# FETs.net
KiCad netlist of a schematic drawn in Altium Designer
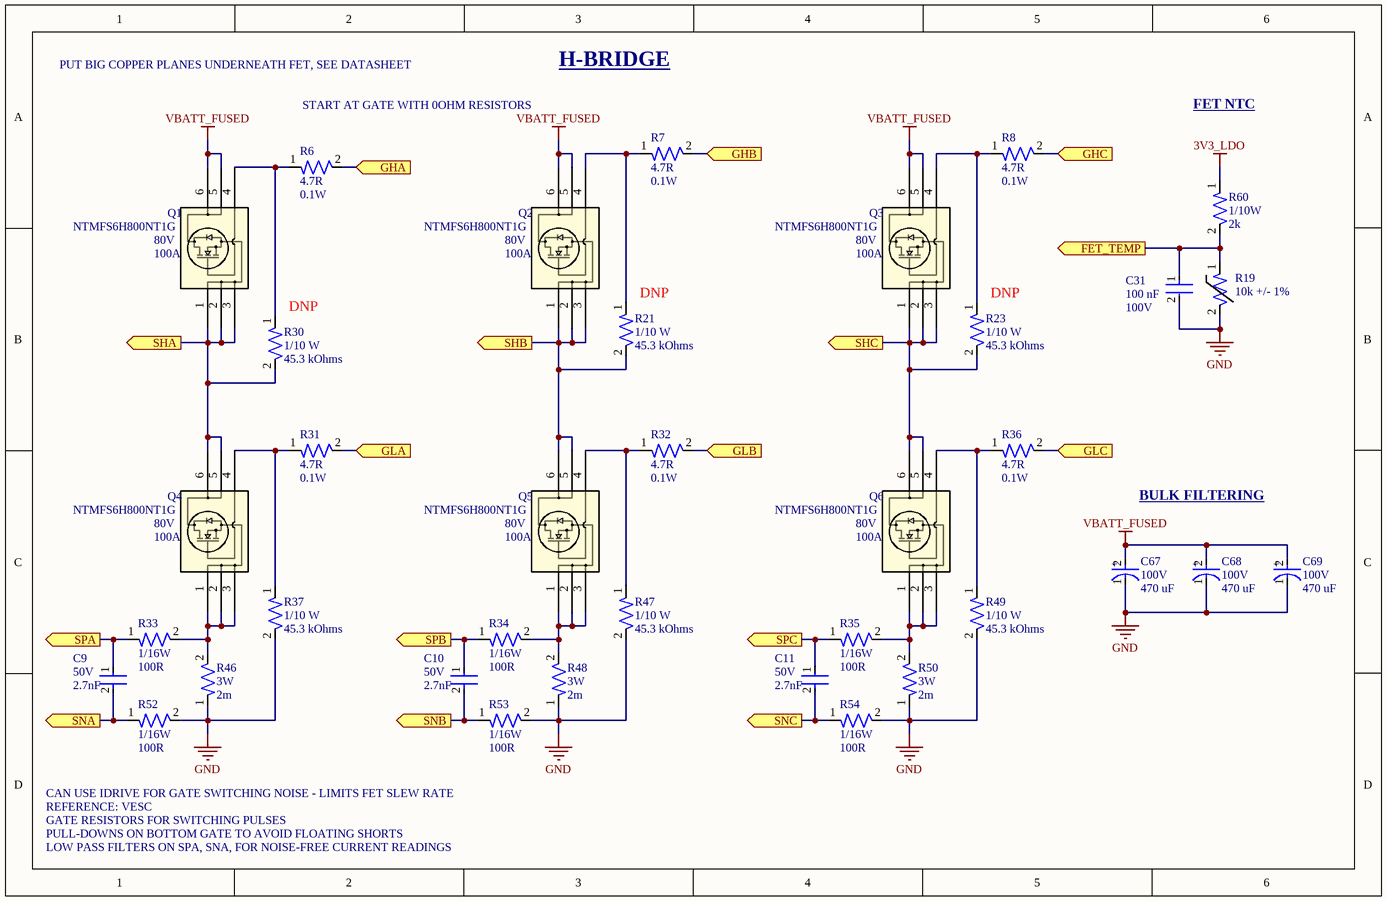
[diagram p0: FETs.SchDoc]

(export (version "E")
  (design (tool "Eeschema 10.0.6"))
  (components
    (comp (ref "C9")
      (value "GRM2165C1H272JA01D")
      (footprint "CAP-0805")
      (description "CAP CER 2700PF 50V C0G/NP0 0805")
      (fields (field (name "VOLTAGE") "50V") (field (name "CAPACITANCE") "2.7nF"))
      (libsource (lib "JLC_25") (part "CAP-2.7N-0001"))
    )
    (comp (ref "C10")
      (value "GRM2165C1H272JA01D")
      (footprint "CAP-0805")
      (description "CAP CER 2700PF 50V C0G/NP0 0805")
      (fields (field (name "VOLTAGE") "50V") (field (name "CAPACITANCE") "2.7nF"))
      (libsource (lib "JLC_25") (part "CAP-2.7N-0001"))
    )
    (comp (ref "C11")
      (value "GRM2165C1H272JA01D")
      (footprint "CAP-0805")
      (description "CAP CER 2700PF 50V C0G/NP0 0805")
      (fields (field (name "VOLTAGE") "50V") (field (name "CAPACITANCE") "2.7nF"))
      (libsource (lib "JLC_25") (part "CAP-2.7N-0001"))
    )
    (comp (ref "C31")
      (value "GRM188R72A104KA35D")
      (footprint "CAP-0603")
      (description "CAP CER 100NF 100V X7R 0603")
      (fields (field (name "CAPACITANCE") "100 nF") (field (name "VOLTAGE") "100V"))
      (libsource (lib "JLC_25") (part "CAP-1U-0002"))
    )
    (comp (ref "C67")
      (value "ESH477M100AM2AA")
      (footprint "CAP-470U-0001")
      (description "CAP ALUM 470UF 20% 100V RADIAL")
      (fields (field (name "VOLTAGE") "100V") (field (name "CAPACITANCE") "470 uF"))
      (libsource (lib "JLC_25") (part "CAP-470U-0001"))
    )
    (comp (ref "C68")
      (value "ESH477M100AM2AA")
      (footprint "CAP-470U-0001")
      (description "CAP ALUM 470UF 20% 100V RADIAL")
      (fields (field (name "VOLTAGE") "100V") (field (name "CAPACITANCE") "470 uF"))
      (libsource (lib "JLC_25") (part "CAP-470U-0001"))
    )
    (comp (ref "C69")
      (value "ESH477M100AM2AA")
      (footprint "CAP-470U-0001")
      (description "CAP ALUM 470UF 20% 100V RADIAL")
      (fields (field (name "VOLTAGE") "100V") (field (name "CAPACITANCE") "470 uF"))
      (libsource (lib "JLC_25") (part "CAP-470U-0001"))
    )
    (comp (ref "Q1")
      (value "NTMFS6H800NT1G")
      (footprint "DFN6_5X6_SO8FL_488AA_ONS")
      (description "N-Channel 80 V 28A (Ta), 203A (Tc) 3.8W (Ta), 200W (Tc) Surface Mount 5-DFN (5x6) (8-SOFL)")
      (fields
        (field (name "MANUFACTURER_PART_NUMBER") "TPH2R506PL")
        (field (name "VDSS") "80V")
        (field (name "DRAIN CURRENT") "100A")
      )
      (libsource (lib "MasterLib") (part "NTMFS6H800NT1G"))
    )
    (comp (ref "Q2")
      (value "NTMFS6H800NT1G")
      (footprint "DFN6_5X6_SO8FL_488AA_ONS")
      (description "N-Channel 80 V 28A (Ta), 203A (Tc) 3.8W (Ta), 200W (Tc) Surface Mount 5-DFN (5x6) (8-SOFL)")
      (fields
        (field (name "MANUFACTURER_PART_NUMBER") "TPH2R506PL")
        (field (name "VDSS") "80V")
        (field (name "DRAIN CURRENT") "100A")
      )
      (libsource (lib "MasterLib") (part "NTMFS6H800NT1G"))
    )
    (comp (ref "Q3")
      (value "NTMFS6H800NT1G")
      (footprint "DFN6_5X6_SO8FL_488AA_ONS")
      (description "N-Channel 80 V 28A (Ta), 203A (Tc) 3.8W (Ta), 200W (Tc) Surface Mount 5-DFN (5x6) (8-SOFL)")
      (fields
        (field (name "MANUFACTURER_PART_NUMBER") "TPH2R506PL")
        (field (name "VDSS") "80V")
        (field (name "DRAIN CURRENT") "100A")
      )
      (libsource (lib "MasterLib") (part "NTMFS6H800NT1G"))
    )
    (comp (ref "Q4")
      (value "NTMFS6H800NT1G")
      (footprint "DFN6_5X6_SO8FL_488AA_ONS")
      (description "N-Channel 80 V 28A (Ta), 203A (Tc) 3.8W (Ta), 200W (Tc) Surface Mount 5-DFN (5x6) (8-SOFL)")
      (fields
        (field (name "MANUFACTURER_PART_NUMBER") "TPH2R506PL")
        (field (name "VDSS") "80V")
        (field (name "DRAIN CURRENT") "100A")
      )
      (libsource (lib "MasterLib") (part "NTMFS6H800NT1G"))
    )
    (comp (ref "Q5")
      (value "NTMFS6H800NT1G")
      (footprint "DFN6_5X6_SO8FL_488AA_ONS")
      (description "N-Channel 80 V 28A (Ta), 203A (Tc) 3.8W (Ta), 200W (Tc) Surface Mount 5-DFN (5x6) (8-SOFL)")
      (fields
        (field (name "MANUFACTURER_PART_NUMBER") "TPH2R506PL")
        (field (name "VDSS") "80V")
        (field (name "DRAIN CURRENT") "100A")
      )
      (libsource (lib "MasterLib") (part "NTMFS6H800NT1G"))
    )
    (comp (ref "Q6")
      (value "NTMFS6H800NT1G")
      (footprint "DFN6_5X6_SO8FL_488AA_ONS")
      (description "N-Channel 80 V 28A (Ta), 203A (Tc) 3.8W (Ta), 200W (Tc) Surface Mount 5-DFN (5x6) (8-SOFL)")
      (fields
        (field (name "MANUFACTURER_PART_NUMBER") "TPH2R506PL")
        (field (name "VDSS") "80V")
        (field (name "DRAIN CURRENT") "100A")
      )
      (libsource (lib "MasterLib") (part "NTMFS6H800NT1G"))
    )
    (comp (ref "R6")
      (value "RMCF0603FT4R70")
      (footprint "RES-0603")
      (description "4.7 Ohms ±1% 0.1W, 1/10W Chip Resistor 0603 (1608 Metric) Automotive AEC-Q200 Thick Film")
      (fields
        (field (name "TOLERANCE") "1%")
        (field (name "RESISTANCE") "4.7R")
        (field (name "POWER") "0.1W")
      )
      (libsource (lib "JLC_25") (part "RES-4.7-0001"))
    )
    (comp (ref "R7")
      (value "RMCF0603FT4R70")
      (footprint "RES-0603")
      (description "4.7 Ohms ±1% 0.1W, 1/10W Chip Resistor 0603 (1608 Metric) Automotive AEC-Q200 Thick Film")
      (fields
        (field (name "TOLERANCE") "1%")
        (field (name "RESISTANCE") "4.7R")
        (field (name "POWER") "0.1W")
      )
      (libsource (lib "JLC_25") (part "RES-4.7-0001"))
    )
    (comp (ref "R8")
      (value "RMCF0603FT4R70")
      (footprint "RES-0603")
      (description "4.7 Ohms ±1% 0.1W, 1/10W Chip Resistor 0603 (1608 Metric) Automotive AEC-Q200 Thick Film")
      (fields
        (field (name "TOLERANCE") "1%")
        (field (name "RESISTANCE") "4.7R")
        (field (name "POWER") "0.1W")
      )
      (libsource (lib "JLC_25") (part "RES-4.7-0001"))
    )
    (comp (ref "R19")
      (value "NCU18XH103F60RB")
      (footprint "RES-0603")
      (description "NTC Thermistor 10k 0603 (1608 Metric)")
      (fields
        (field (name "MANUFACTURER PART NUMBER") "TMP6431DECR")
        (field (name "MANUFACTURER") "Texas Instruments")
        (field (name "RESISTANCE") "10k +/- 1%")
      )
      (libsource (lib "MasterLib") (part "THERM-10K-0001"))
    )
    (comp (ref "R21")
      (value "RC0603FR-0745K3L")
      (footprint "RES-0603")
      (description "45.3 kOhms ±1% 0.1W, 1/10W Chip Resistor 0603 (1608 Metric) Moisture Resistant Thick Film")
      (fields
        (field (name "TOLERANCE") "+/- 1%")
        (field (name "POWER") "1/10 W")
        (field (name "RESISTANCE") "45.3 kOhms")
      )
      (libsource (lib "MasterLib") (part "RES-45.3K-0001"))
    )
    (comp (ref "R23")
      (value "RC0603FR-0745K3L")
      (footprint "RES-0603")
      (description "45.3 kOhms ±1% 0.1W, 1/10W Chip Resistor 0603 (1608 Metric) Moisture Resistant Thick Film")
      (fields
        (field (name "TOLERANCE") "+/- 1%")
        (field (name "POWER") "1/10 W")
        (field (name "RESISTANCE") "45.3 kOhms")
      )
      (libsource (lib "MasterLib") (part "RES-45.3K-0001"))
    )
    (comp (ref "R30")
      (value "RC0603FR-0745K3L")
      (footprint "RES-0603")
      (description "45.3 kOhms ±1% 0.1W, 1/10W Chip Resistor 0603 (1608 Metric) Moisture Resistant Thick Film")
      (fields
        (field (name "TOLERANCE") "+/- 1%")
        (field (name "POWER") "1/10 W")
        (field (name "RESISTANCE") "45.3 kOhms")
      )
      (libsource (lib "MasterLib") (part "RES-45.3K-0001"))
    )
    (comp (ref "R31")
      (value "RMCF0603FT4R70")
      (footprint "RES-0603")
      (description "4.7 Ohms ±1% 0.1W, 1/10W Chip Resistor 0603 (1608 Metric) Automotive AEC-Q200 Thick Film")
      (fields
        (field (name "TOLERANCE") "1%")
        (field (name "RESISTANCE") "4.7R")
        (field (name "POWER") "0.1W")
      )
      (libsource (lib "JLC_25") (part "RES-4.7-0001"))
    )
    (comp (ref "R32")
      (value "RMCF0603FT4R70")
      (footprint "RES-0603")
      (description "4.7 Ohms ±1% 0.1W, 1/10W Chip Resistor 0603 (1608 Metric) Automotive AEC-Q200 Thick Film")
      (fields
        (field (name "TOLERANCE") "1%")
        (field (name "RESISTANCE") "4.7R")
        (field (name "POWER") "0.1W")
      )
      (libsource (lib "JLC_25") (part "RES-4.7-0001"))
    )
    (comp (ref "R33")
      (value "RC0402FR-07100RL")
      (footprint "RES-0402")
      (description "RES 100 OHM 1% 1/16W 0402")
      (fields
        (field (name "TOLERANCE") "1%")
        (field (name "POWER") "1/16W")
        (field (name "RESISTANCE") "100R")
      )
      (libsource (lib "JLC_25") (part "RES-100-0001"))
    )
    (comp (ref "R34")
      (value "RC0402FR-07100RL")
      (footprint "RES-0402")
      (description "RES 100 OHM 1% 1/16W 0402")
      (fields
        (field (name "TOLERANCE") "1%")
        (field (name "POWER") "1/16W")
        (field (name "RESISTANCE") "100R")
      )
      (libsource (lib "JLC_25") (part "RES-100-0001"))
    )
    (comp (ref "R35")
      (value "RC0402FR-07100RL")
      (footprint "RES-0402")
      (description "RES 100 OHM 1% 1/16W 0402")
      (fields
        (field (name "TOLERANCE") "1%")
        (field (name "POWER") "1/16W")
        (field (name "RESISTANCE") "100R")
      )
      (libsource (lib "JLC_25") (part "RES-100-0001"))
    )
    (comp (ref "R36")
      (value "RMCF0603FT4R70")
      (footprint "RES-0603")
      (description "4.7 Ohms ±1% 0.1W, 1/10W Chip Resistor 0603 (1608 Metric) Automotive AEC-Q200 Thick Film")
      (fields
        (field (name "TOLERANCE") "1%")
        (field (name "RESISTANCE") "4.7R")
        (field (name "POWER") "0.1W")
      )
      (libsource (lib "JLC_25") (part "RES-4.7-0001"))
    )
    (comp (ref "R37")
      (value "RC0603FR-0745K3L")
      (footprint "RES-0603")
      (description "45.3 kOhms ±1% 0.1W, 1/10W Chip Resistor 0603 (1608 Metric) Moisture Resistant Thick Film")
      (fields
        (field (name "TOLERANCE") "+/- 1%")
        (field (name "POWER") "1/10 W")
        (field (name "RESISTANCE") "45.3 kOhms")
      )
      (libsource (lib "MasterLib") (part "RES-45.3K-0001"))
    )
    (comp (ref "R46")
      (value "CSNL2512FT2L00")
      (footprint "STA_CSNL25122_STP")
      (description "2 mOhms ±1% 3W Chip Resistor 2512 (6332 Metric) Current Sense, Moisture Resistant Metal Element")
      (fields (field (name "TOLERANCE") "1%") (field (name "POWER") "3W") (field (name "RESISTANCE") "2m"))
      (libsource (lib "JLC_25") (part "RES-2m-0001"))
    )
    (comp (ref "R47")
      (value "RC0603FR-0745K3L")
      (footprint "RES-0603")
      (description "45.3 kOhms ±1% 0.1W, 1/10W Chip Resistor 0603 (1608 Metric) Moisture Resistant Thick Film")
      (fields
        (field (name "TOLERANCE") "+/- 1%")
        (field (name "POWER") "1/10 W")
        (field (name "RESISTANCE") "45.3 kOhms")
      )
      (libsource (lib "MasterLib") (part "RES-45.3K-0001"))
    )
    (comp (ref "R48")
      (value "CSNL2512FT2L00")
      (footprint "STA_CSNL25122_STP")
      (description "2 mOhms ±1% 3W Chip Resistor 2512 (6332 Metric) Current Sense, Moisture Resistant Metal Element")
      (fields (field (name "TOLERANCE") "1%") (field (name "POWER") "3W") (field (name "RESISTANCE") "2m"))
      (libsource (lib "JLC_25") (part "RES-2m-0001"))
    )
    (comp (ref "R49")
      (value "RC0603FR-0745K3L")
      (footprint "RES-0603")
      (description "45.3 kOhms ±1% 0.1W, 1/10W Chip Resistor 0603 (1608 Metric) Moisture Resistant Thick Film")
      (fields
        (field (name "TOLERANCE") "+/- 1%")
        (field (name "POWER") "1/10 W")
        (field (name "RESISTANCE") "45.3 kOhms")
      )
      (libsource (lib "MasterLib") (part "RES-45.3K-0001"))
    )
    (comp (ref "R50")
      (value "CSNL2512FT2L00")
      (footprint "STA_CSNL25122_STP")
      (description "2 mOhms ±1% 3W Chip Resistor 2512 (6332 Metric) Current Sense, Moisture Resistant Metal Element")
      (fields (field (name "TOLERANCE") "1%") (field (name "POWER") "3W") (field (name "RESISTANCE") "2m"))
      (libsource (lib "JLC_25") (part "RES-2m-0001"))
    )
    (comp (ref "R52")
      (value "RC0402FR-07100RL")
      (footprint "RES-0402")
      (description "RES 100 OHM 1% 1/16W 0402")
      (fields
        (field (name "TOLERANCE") "1%")
        (field (name "POWER") "1/16W")
        (field (name "RESISTANCE") "100R")
      )
      (libsource (lib "JLC_25") (part "RES-100-0001"))
    )
    (comp (ref "R53")
      (value "RC0402FR-07100RL")
      (footprint "RES-0402")
      (description "RES 100 OHM 1% 1/16W 0402")
      (fields
        (field (name "TOLERANCE") "1%")
        (field (name "POWER") "1/16W")
        (field (name "RESISTANCE") "100R")
      )
      (libsource (lib "JLC_25") (part "RES-100-0001"))
    )
    (comp (ref "R54")
      (value "RC0402FR-07100RL")
      (footprint "RES-0402")
      (description "RES 100 OHM 1% 1/16W 0402")
      (fields
        (field (name "TOLERANCE") "1%")
        (field (name "POWER") "1/16W")
        (field (name "RESISTANCE") "100R")
      )
      (libsource (lib "JLC_25") (part "RES-100-0001"))
    )
    (comp (ref "R60")
      (value "RC0603JR-072KL")
      (footprint "RES-0603")
      (description "RES 2K OHM 5% 1/10W 0603")
      (fields (field (name "POWER") "1/10W") (field (name "RESISTANCE") "2k"))
      (libsource (lib "JLC_25") (part "RES-13.7K-0001"))
    )
  )
  (nets
    (net (code "1") (name "/FET_TEMP") (class "Default")
      (node (ref "C31") (pin "1") (pinfunction "1_1") (pintype "passive"))
      (node (ref "R19") (pin "1") (pinfunction "1_1") (pintype "passive"))
      (node (ref "R60") (pin "2") (pinfunction "2_2") (pintype "passive"))
    )
    (net (code "2") (name "/GHA") (class "Default")
      (node (ref "R6") (pin "2") (pinfunction "2_2") (pintype "passive"))
    )
    (net (code "3") (name "/GHB") (class "Default")
      (node (ref "R7") (pin "2") (pinfunction "2_2") (pintype "passive"))
    )
    (net (code "4") (name "/GHC") (class "Default")
      (node (ref "R8") (pin "2") (pinfunction "2_2") (pintype "passive"))
    )
    (net (code "5") (name "/GLA") (class "Default")
      (node (ref "R31") (pin "2") (pinfunction "2_2") (pintype "passive"))
    )
    (net (code "6") (name "/GLB") (class "Default")
      (node (ref "R32") (pin "2") (pinfunction "2_2") (pintype "passive"))
    )
    (net (code "7") (name "/GLC") (class "Default")
      (node (ref "R36") (pin "2") (pinfunction "2_2") (pintype "passive"))
    )
    (net (code "8") (name "/SHA") (class "Default")
      (node (ref "Q1") (pin "1") (pinfunction "1_1") (pintype "passive"))
      (node (ref "Q1") (pin "2") (pinfunction "2_2") (pintype "passive"))
      (node (ref "Q1") (pin "3") (pinfunction "3_3") (pintype "passive"))
      (node (ref "Q4") (pin "5") (pinfunction "5_5") (pintype "passive"))
      (node (ref "Q4") (pin "6") (pinfunction "6_6") (pintype "passive"))
      (node (ref "R30") (pin "2") (pinfunction "2_2") (pintype "passive"))
    )
    (net (code "9") (name "/SHB") (class "Default")
      (node (ref "Q2") (pin "1") (pinfunction "1_1") (pintype "passive"))
      (node (ref "Q2") (pin "2") (pinfunction "2_2") (pintype "passive"))
      (node (ref "Q2") (pin "3") (pinfunction "3_3") (pintype "passive"))
      (node (ref "Q5") (pin "5") (pinfunction "5_5") (pintype "passive"))
      (node (ref "Q5") (pin "6") (pinfunction "6_6") (pintype "passive"))
      (node (ref "R21") (pin "2") (pinfunction "2_2") (pintype "passive"))
    )
    (net (code "10") (name "/SHC") (class "Default")
      (node (ref "Q3") (pin "1") (pinfunction "1_1") (pintype "passive"))
      (node (ref "Q3") (pin "2") (pinfunction "2_2") (pintype "passive"))
      (node (ref "Q3") (pin "3") (pinfunction "3_3") (pintype "passive"))
      (node (ref "Q6") (pin "5") (pinfunction "5_5") (pintype "passive"))
      (node (ref "Q6") (pin "6") (pinfunction "6_6") (pintype "passive"))
      (node (ref "R23") (pin "2") (pinfunction "2_2") (pintype "passive"))
    )
    (net (code "11") (name "/SNA") (class "Default")
      (node (ref "C9") (pin "2") (pinfunction "2_2") (pintype "passive"))
      (node (ref "R52") (pin "1") (pinfunction "1_1") (pintype "passive"))
    )
    (net (code "12") (name "/SNB") (class "Default")
      (node (ref "C10") (pin "2") (pinfunction "2_2") (pintype "passive"))
      (node (ref "R53") (pin "1") (pinfunction "1_1") (pintype "passive"))
    )
    (net (code "13") (name "/SNC") (class "Default")
      (node (ref "C11") (pin "2") (pinfunction "2_2") (pintype "passive"))
      (node (ref "R54") (pin "1") (pinfunction "1_1") (pintype "passive"))
    )
    (net (code "14") (name "/SPA") (class "Default")
      (node (ref "C9") (pin "1") (pinfunction "1_1") (pintype "passive"))
      (node (ref "R33") (pin "1") (pinfunction "1_1") (pintype "passive"))
    )
    (net (code "15") (name "/SPB") (class "Default")
      (node (ref "C10") (pin "1") (pinfunction "1_1") (pintype "passive"))
      (node (ref "R34") (pin "1") (pinfunction "1_1") (pintype "passive"))
    )
    (net (code "16") (name "/SPC") (class "Default")
      (node (ref "C11") (pin "1") (pinfunction "1_1") (pintype "passive"))
      (node (ref "R35") (pin "1") (pinfunction "1_1") (pintype "passive"))
    )
    (net (code "17") (name "3V3_LDO") (class "Default")
      (node (ref "R60") (pin "1") (pinfunction "1_1") (pintype "passive"))
    )
    (net (code "18") (name "GND") (class "Default")
      (node (ref "C31") (pin "2") (pinfunction "2_2") (pintype "passive"))
      (node (ref "C67") (pin "1") (pinfunction "2_1") (pintype "passive"))
      (node (ref "C68") (pin "1") (pinfunction "2_1") (pintype "passive"))
      (node (ref "C69") (pin "1") (pinfunction "2_1") (pintype "passive"))
      (node (ref "R19") (pin "2") (pinfunction "2_2") (pintype "passive"))
      (node (ref "R37") (pin "2") (pinfunction "2_2") (pintype "passive"))
      (node (ref "R46") (pin "1") (pinfunction "1_1") (pintype "passive"))
      (node (ref "R47") (pin "2") (pinfunction "2_2") (pintype "passive"))
      (node (ref "R48") (pin "1") (pinfunction "1_1") (pintype "passive"))
      (node (ref "R49") (pin "2") (pinfunction "2_2") (pintype "passive"))
      (node (ref "R50") (pin "1") (pinfunction "1_1") (pintype "passive"))
      (node (ref "R52") (pin "2") (pinfunction "2_2") (pintype "passive"))
      (node (ref "R53") (pin "2") (pinfunction "2_2") (pintype "passive"))
      (node (ref "R54") (pin "2") (pinfunction "2_2") (pintype "passive"))
    )
    (net (code "19") (name "Net-(Q1-Pad4)") (class "Default")
      (node (ref "Q1") (pin "4") (pinfunction "4_4") (pintype "passive"))
      (node (ref "R30") (pin "1") (pinfunction "1_1") (pintype "passive"))
      (node (ref "R6") (pin "1") (pinfunction "1_1") (pintype "passive"))
    )
    (net (code "20") (name "Net-(Q2-Pad4)") (class "Default")
      (node (ref "Q2") (pin "4") (pinfunction "4_4") (pintype "passive"))
      (node (ref "R21") (pin "1") (pinfunction "1_1") (pintype "passive"))
      (node (ref "R7") (pin "1") (pinfunction "1_1") (pintype "passive"))
    )
    (net (code "21") (name "Net-(Q3-Pad4)") (class "Default")
      (node (ref "Q3") (pin "4") (pinfunction "4_4") (pintype "passive"))
      (node (ref "R23") (pin "1") (pinfunction "1_1") (pintype "passive"))
      (node (ref "R8") (pin "1") (pinfunction "1_1") (pintype "passive"))
    )
    (net (code "22") (name "Net-(Q4-Pad1)") (class "Default")
      (node (ref "Q4") (pin "1") (pinfunction "1_1") (pintype "passive"))
      (node (ref "Q4") (pin "2") (pinfunction "2_2") (pintype "passive"))
      (node (ref "Q4") (pin "3") (pinfunction "3_3") (pintype "passive"))
      (node (ref "R33") (pin "2") (pinfunction "2_2") (pintype "passive"))
      (node (ref "R46") (pin "2") (pinfunction "2_2") (pintype "passive"))
    )
    (net (code "23") (name "Net-(Q4-Pad4)") (class "Default")
      (node (ref "Q4") (pin "4") (pinfunction "4_4") (pintype "passive"))
      (node (ref "R31") (pin "1") (pinfunction "1_1") (pintype "passive"))
      (node (ref "R37") (pin "1") (pinfunction "1_1") (pintype "passive"))
    )
    (net (code "24") (name "Net-(Q5-Pad1)") (class "Default")
      (node (ref "Q5") (pin "1") (pinfunction "1_1") (pintype "passive"))
      (node (ref "Q5") (pin "2") (pinfunction "2_2") (pintype "passive"))
      (node (ref "Q5") (pin "3") (pinfunction "3_3") (pintype "passive"))
      (node (ref "R34") (pin "2") (pinfunction "2_2") (pintype "passive"))
      (node (ref "R48") (pin "2") (pinfunction "2_2") (pintype "passive"))
    )
    (net (code "25") (name "Net-(Q5-Pad4)") (class "Default")
      (node (ref "Q5") (pin "4") (pinfunction "4_4") (pintype "passive"))
      (node (ref "R32") (pin "1") (pinfunction "1_1") (pintype "passive"))
      (node (ref "R47") (pin "1") (pinfunction "1_1") (pintype "passive"))
    )
    (net (code "26") (name "Net-(Q6-Pad1)") (class "Default")
      (node (ref "Q6") (pin "1") (pinfunction "1_1") (pintype "passive"))
      (node (ref "Q6") (pin "2") (pinfunction "2_2") (pintype "passive"))
      (node (ref "Q6") (pin "3") (pinfunction "3_3") (pintype "passive"))
      (node (ref "R35") (pin "2") (pinfunction "2_2") (pintype "passive"))
      (node (ref "R50") (pin "2") (pinfunction "2_2") (pintype "passive"))
    )
    (net (code "27") (name "Net-(Q6-Pad4)") (class "Default")
      (node (ref "Q6") (pin "4") (pinfunction "4_4") (pintype "passive"))
      (node (ref "R36") (pin "1") (pinfunction "1_1") (pintype "passive"))
      (node (ref "R49") (pin "1") (pinfunction "1_1") (pintype "passive"))
    )
    (net (code "28") (name "VBATT_FUSED") (class "Default")
      (node (ref "C67") (pin "2") (pinfunction "1_2") (pintype "passive"))
      (node (ref "C68") (pin "2") (pinfunction "1_2") (pintype "passive"))
      (node (ref "C69") (pin "2") (pinfunction "1_2") (pintype "passive"))
      (node (ref "Q1") (pin "5") (pinfunction "5_5") (pintype "passive"))
      (node (ref "Q1") (pin "6") (pinfunction "6_6") (pintype "passive"))
      (node (ref "Q2") (pin "5") (pinfunction "5_5") (pintype "passive"))
      (node (ref "Q2") (pin "6") (pinfunction "6_6") (pintype "passive"))
      (node (ref "Q3") (pin "5") (pinfunction "5_5") (pintype "passive"))
      (node (ref "Q3") (pin "6") (pinfunction "6_6") (pintype "passive"))
    )
  )
)
